# 05-USB-UART.net
KiCad netlist of a schematic drawn in Altium Designer
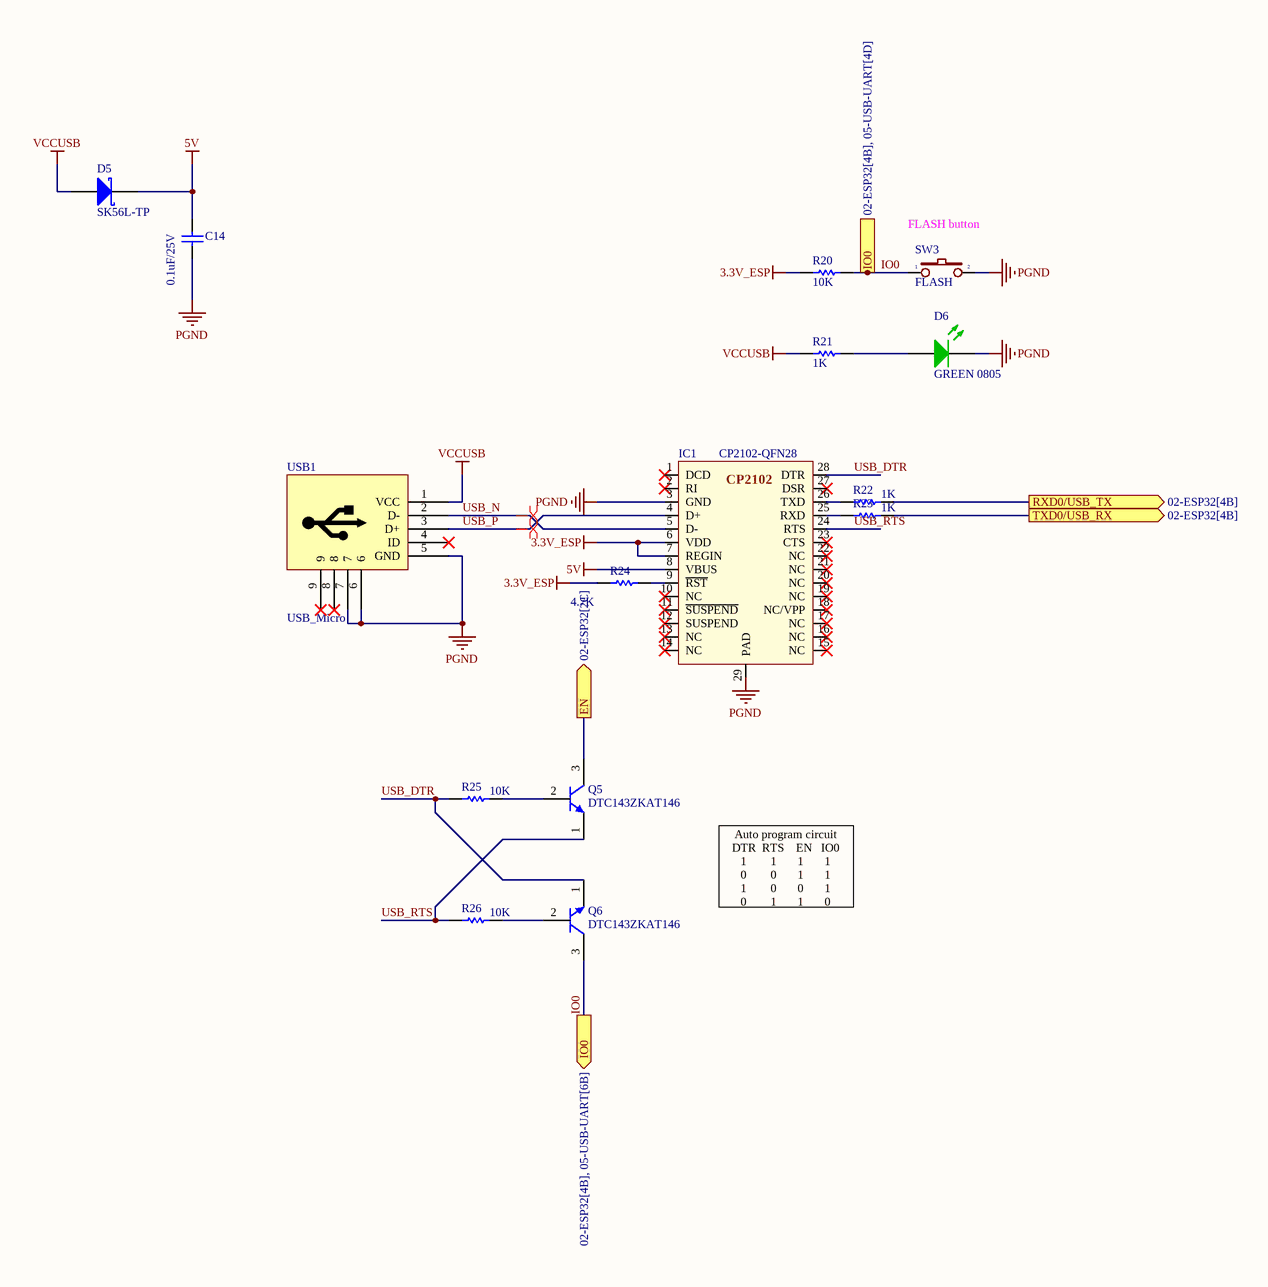
[diagram p0: 05-USB-UART.SchDoc]

(export (version "E")
  (design (tool "Eeschema 10.0.6"))
  (components
    (comp (ref "C14")
      (value "0.1uF/25V")
      (footprint "CAP_CERA_C2012(CC0805INCH)")
      (description "0.1µF ±10% 25V Ceramic Capacitor X7R 0805 (2012 Metric)")
      (libsource (lib "GSHT_181013") (part "0.1uF/50V/C0603/10%"))
    )
    (comp (ref "D5")
      (value "SK56L-TP")
      (footprint "30# SK56L-TPMSCT-ND")
      (description "DIODE SCHOTTKY 60V 5A DO214AB")
      (libsource (lib "GSHT_181013") (part "30# SK56L-TP"))
    )
    (comp (ref "D6")
      (value "GREEN 0805")
      (footprint "Led 0805G")
      (description "Green 571nm LED Indication - Discrete 2V 0805 (2012 Metric)")
      (libsource (lib "GSHT_181013") (part "LED GREEN 0603"))
    )
    (comp (ref "IC1")
      (value "CP2102-QFN28")
      (footprint "CP2102-QFN28")
      (description "USB Bridge, USB to UART USB 2.0 UART Interface 28-QFN (5x5)")
      (libsource (lib "lpson") (part "CP2102"))
    )
    (comp (ref "Q5")
      (value "DTC143ZKAT146")
      (footprint "6# DTC143ZKAT146-E")
      (description "Pre-Biased Bipolar Transistor (BJT) NPN - Pre-Biased 50V 100mA 250MHz 200mW Surface Mount SMT3")
      (libsource (lib "GSHT_181013") (part "6#DTC143ZKAT146"))
    )
    (comp (ref "Q6")
      (value "DTC143ZKAT146")
      (footprint "6# DTC143ZKAT146-E")
      (description "Pre-Biased Bipolar Transistor (BJT) NPN - Pre-Biased 50V 100mA 250MHz 200mW Surface Mount SMT3")
      (libsource (lib "GSHT_181013") (part "6#DTC143ZKAT146"))
    )
    (comp (ref "R20")
      (value "10K")
      (footprint "Res 0805 SMD")
      (description "10 kOhms ±1% 0.125W, 1/8W Chip Resistor 0805 (2012 Metric) Thick Film")
      (libsource (lib "GSHT_181013") (part "200K/R0603/1%"))
    )
    (comp (ref "R21")
      (value "1K")
      (footprint "Res 0805 SMD")
      (description "1 kOhms ±1% 0.125W, 1/8W Chip Resistor 0805 (2012 Metric) Automotive AEC-Q200 Thick Film")
      (libsource (lib "GSHT_181013") (part "200K/R0603/1%"))
    )
    (comp (ref "R22")
      (value "1K")
      (footprint "Res 0805 SMD")
      (description "1 kOhms ±1% 0.125W, 1/8W Chip Resistor 0805 (2012 Metric) Automotive AEC-Q200 Thick Film")
      (libsource (lib "GSHT_181013") (part "34.8K/R0805/1%"))
    )
    (comp (ref "R23")
      (value "1K")
      (footprint "Res 0805 SMD")
      (description "1 kOhms ±1% 0.125W, 1/8W Chip Resistor 0805 (2012 Metric) Automotive AEC-Q200 Thick Film")
      (libsource (lib "GSHT_181013") (part "34.8K/R0805/1%"))
    )
    (comp (ref "R24")
      (value "4.7K")
      (footprint "Res 0805 SMD")
      (description "4.7 kOhms ±1% 0.125W, 1/8W Chip Resistor 0805 (2012 Metric) Thick Film")
      (libsource (lib "GSHT_181013") (part "34.8K/R0805/1%"))
    )
    (comp (ref "R25")
      (value "10K")
      (footprint "Res 0805 SMD")
      (description "10 kOhms ±1% 0.125W, 1/8W Chip Resistor 0805 (2012 Metric) Thick Film")
      (libsource (lib "GSHT_181013") (part "34.8K/R0805/1%"))
    )
    (comp (ref "R26")
      (value "10K")
      (footprint "Res 0805 SMD")
      (description "10 kOhms ±1% 0.125W, 1/8W Chip Resistor 0805 (2012 Metric) Thick Film")
      (libsource (lib "GSHT_181013") (part "34.8K/R0805/1%"))
    )
    (comp (ref "SW3")
      (value "FLASH")
      (footprint "Button 3x4mm")
      (description "SWITCH TACTILE SPST-NO 0.05A 12V")
      (libsource (lib "lpson") (part "SW2"))
    )
    (comp (ref "USB1")
      (value "USB_Micro")
      (footprint "USB_MICRO_B - Digikey")
      (description "USB - micro B USB 2.0 Receptacle Connector 5 Position Surface Mount, Right Angle; Through Hole")
      (libsource (lib "lpson") (part "USB_MINI"))
    )
  )
  (nets
    (net (code "1") (name "/EN") (class "Default")
      (node (ref "Q5") (pin "3") (pinfunction "C_3") (pintype "passive"))
    )
    (net (code "2") (name "/IO0") (class "Default")
      (node (ref "Q6") (pin "3") (pinfunction "C_3") (pintype "passive"))
      (node (ref "R20") (pin "2") (pinfunction "2_2") (pintype "passive"))
      (node (ref "SW3") (pin "1") (pinfunction "1_1") (pintype "passive"))
    )
    (net (code "3") (name "/RXD0{slash}USB_TX") (class "Default")
      (node (ref "R22") (pin "1") (pinfunction "1_1") (pintype "passive"))
    )
    (net (code "4") (name "/TXD0{slash}USB_RX") (class "Default")
      (node (ref "R23") (pin "1") (pinfunction "1_1") (pintype "passive"))
    )
    (net (code "5") (name "/USB_DTR") (class "Default")
      (node (ref "IC1") (pin "28") (pinfunction "DTR_28") (pintype "passive"))
      (node (ref "Q6") (pin "1") (pinfunction "E_1") (pintype "passive"))
      (node (ref "R25") (pin "2") (pinfunction "2_2") (pintype "passive"))
    )
    (net (code "6") (name "/USB_N") (class "Default")
      (node (ref "IC1") (pin "5") (pinfunction "D-_5") (pintype "passive"))
      (node (ref "USB1") (pin "2") (pinfunction "D-_2") (pintype "passive"))
    )
    (net (code "7") (name "/USB_P") (class "Default")
      (node (ref "IC1") (pin "4") (pinfunction "D+_4") (pintype "passive"))
      (node (ref "USB1") (pin "3") (pinfunction "D+_3") (pintype "passive"))
    )
    (net (code "8") (name "/USB_RTS") (class "Default")
      (node (ref "IC1") (pin "24") (pinfunction "RTS_24") (pintype "passive"))
      (node (ref "Q5") (pin "1") (pinfunction "E_1") (pintype "passive"))
      (node (ref "R26") (pin "2") (pinfunction "2_2") (pintype "passive"))
    )
    (net (code "9") (name "3.3V_ESP") (class "Default")
      (node (ref "IC1") (pin "6") (pinfunction "VDD_6") (pintype "passive"))
      (node (ref "IC1") (pin "7") (pinfunction "REGIN_7") (pintype "passive"))
      (node (ref "R20") (pin "1") (pinfunction "1_1") (pintype "passive"))
      (node (ref "R24") (pin "1") (pinfunction "1_1") (pintype "passive"))
    )
    (net (code "10") (name "5V") (class "Default")
      (node (ref "C14") (pin "2") (pinfunction "2_2") (pintype "passive"))
      (node (ref "D5") (pin "2") (pinfunction "K_2") (pintype "passive"))
      (node (ref "IC1") (pin "8") (pinfunction "VBUS_8") (pintype "passive"))
    )
    (net (code "11") (name "Net-(D6-A)") (class "Default")
      (node (ref "D6") (pin "1") (pinfunction "A_1") (pintype "passive"))
      (node (ref "R21") (pin "2") (pinfunction "2_2") (pintype "passive"))
    )
    (net (code "12") (name "Net-(IC1-RXD)") (class "Default")
      (node (ref "IC1") (pin "25") (pinfunction "RXD_25") (pintype "passive"))
      (node (ref "R23") (pin "2") (pinfunction "2_2") (pintype "passive"))
    )
    (net (code "13") (name "Net-(IC1-TXD)") (class "Default")
      (node (ref "IC1") (pin "26") (pinfunction "TXD_26") (pintype "passive"))
      (node (ref "R22") (pin "2") (pinfunction "2_2") (pintype "passive"))
    )
    (net (code "14") (name "Net-(IC1-~{RST})") (class "Default")
      (node (ref "IC1") (pin "9") (pinfunction "~{RST}_9") (pintype "passive"))
      (node (ref "R24") (pin "2") (pinfunction "2_2") (pintype "passive"))
    )
    (net (code "15") (name "Net-(Q5-B)") (class "Default")
      (node (ref "Q5") (pin "2") (pinfunction "B_2") (pintype "passive"))
      (node (ref "R25") (pin "1") (pinfunction "1_1") (pintype "passive"))
    )
    (net (code "16") (name "Net-(Q6-B)") (class "Default")
      (node (ref "Q6") (pin "2") (pinfunction "B_2") (pintype "passive"))
      (node (ref "R26") (pin "1") (pinfunction "1_1") (pintype "passive"))
    )
    (net (code "17") (name "PGND") (class "Default")
      (node (ref "C14") (pin "1") (pinfunction "1_1") (pintype "passive"))
      (node (ref "D6") (pin "2") (pinfunction "K_2") (pintype "passive"))
      (node (ref "IC1") (pin "29") (pinfunction "PAD_29") (pintype "passive"))
      (node (ref "IC1") (pin "3") (pinfunction "GND_3") (pintype "passive"))
      (node (ref "SW3") (pin "2") (pinfunction "2_2") (pintype "passive"))
      (node (ref "USB1") (pin "5") (pinfunction "GND_5") (pintype "passive"))
      (node (ref "USB1") (pin "6") (pinfunction "6_6") (pintype "passive"))
      (node (ref "USB1") (pin "7") (pinfunction "7_7") (pintype "passive"))
    )
    (net (code "18") (name "VCCUSB") (class "Default")
      (node (ref "D5") (pin "1") (pinfunction "A_1") (pintype "passive"))
      (node (ref "R21") (pin "1") (pinfunction "1_1") (pintype "passive"))
      (node (ref "USB1") (pin "1") (pinfunction "VCC_1") (pintype "passive"))
    )
    (net (code "19") (name "unconnected-(IC1-CTS-Pad23)") (class "Default")
      (node (ref "IC1") (pin "23") (pinfunction "CTS_23") (pintype "passive+no_connect"))
    )
    (net (code "20") (name "unconnected-(IC1-DCD-Pad1)") (class "Default")
      (node (ref "IC1") (pin "1") (pinfunction "DCD_1") (pintype "passive+no_connect"))
    )
    (net (code "21") (name "unconnected-(IC1-DSR-Pad27)") (class "Default")
      (node (ref "IC1") (pin "27") (pinfunction "DSR_27") (pintype "passive+no_connect"))
    )
    (net (code "22") (name "unconnected-(IC1-NC-Pad10)") (class "Default")
      (node (ref "IC1") (pin "10") (pinfunction "NC_10") (pintype "passive+no_connect"))
    )
    (net (code "23") (name "unconnected-(IC1-NC-Pad13)") (class "Default")
      (node (ref "IC1") (pin "13") (pinfunction "NC_13") (pintype "passive+no_connect"))
    )
    (net (code "24") (name "unconnected-(IC1-NC-Pad14)") (class "Default")
      (node (ref "IC1") (pin "14") (pinfunction "NC_14") (pintype "passive+no_connect"))
    )
    (net (code "25") (name "unconnected-(IC1-NC-Pad15)") (class "Default")
      (node (ref "IC1") (pin "15") (pinfunction "NC_15") (pintype "passive+no_connect"))
    )
    (net (code "26") (name "unconnected-(IC1-NC-Pad16)") (class "Default")
      (node (ref "IC1") (pin "16") (pinfunction "NC_16") (pintype "passive+no_connect"))
    )
    (net (code "27") (name "unconnected-(IC1-NC-Pad17)") (class "Default")
      (node (ref "IC1") (pin "17") (pinfunction "NC_17") (pintype "passive+no_connect"))
    )
    (net (code "28") (name "unconnected-(IC1-NC-Pad19)") (class "Default")
      (node (ref "IC1") (pin "19") (pinfunction "NC_19") (pintype "passive+no_connect"))
    )
    (net (code "29") (name "unconnected-(IC1-NC-Pad20)") (class "Default")
      (node (ref "IC1") (pin "20") (pinfunction "NC_20") (pintype "passive+no_connect"))
    )
    (net (code "30") (name "unconnected-(IC1-NC-Pad21)") (class "Default")
      (node (ref "IC1") (pin "21") (pinfunction "NC_21") (pintype "passive+no_connect"))
    )
    (net (code "31") (name "unconnected-(IC1-NC-Pad22)") (class "Default")
      (node (ref "IC1") (pin "22") (pinfunction "NC_22") (pintype "passive+no_connect"))
    )
    (net (code "32") (name "unconnected-(IC1-NC{slash}VPP-Pad18)") (class "Default")
      (node (ref "IC1") (pin "18") (pinfunction "NC/VPP_18") (pintype "passive+no_connect"))
    )
    (net (code "33") (name "unconnected-(IC1-RI-Pad2)") (class "Default")
      (node (ref "IC1") (pin "2") (pinfunction "RI_2") (pintype "passive+no_connect"))
    )
    (net (code "34") (name "unconnected-(IC1-SUSPEND-Pad12)") (class "Default")
      (node (ref "IC1") (pin "12") (pinfunction "SUSPEND_12") (pintype "passive+no_connect"))
    )
    (net (code "35") (name "unconnected-(IC1-~{SUSPEND}-Pad11)") (class "Default")
      (node (ref "IC1") (pin "11") (pinfunction "~{SUSPEND}_11") (pintype "passive+no_connect"))
    )
    (net (code "36") (name "unconnected-(USB1-ID-Pad4)") (class "Default")
      (node (ref "USB1") (pin "4") (pinfunction "ID_4") (pintype "passive+no_connect"))
    )
    (net (code "37") (name "unconnected-(USB1-Pad8)") (class "Default")
      (node (ref "USB1") (pin "8") (pinfunction "8_8") (pintype "passive+no_connect"))
    )
    (net (code "38") (name "unconnected-(USB1-Pad9)") (class "Default")
      (node (ref "USB1") (pin "9") (pinfunction "9_9") (pintype "passive+no_connect"))
    )
  )
)
